# Xadow_Serial.net
KiCad netlist of a schematic drawn in EAGLE
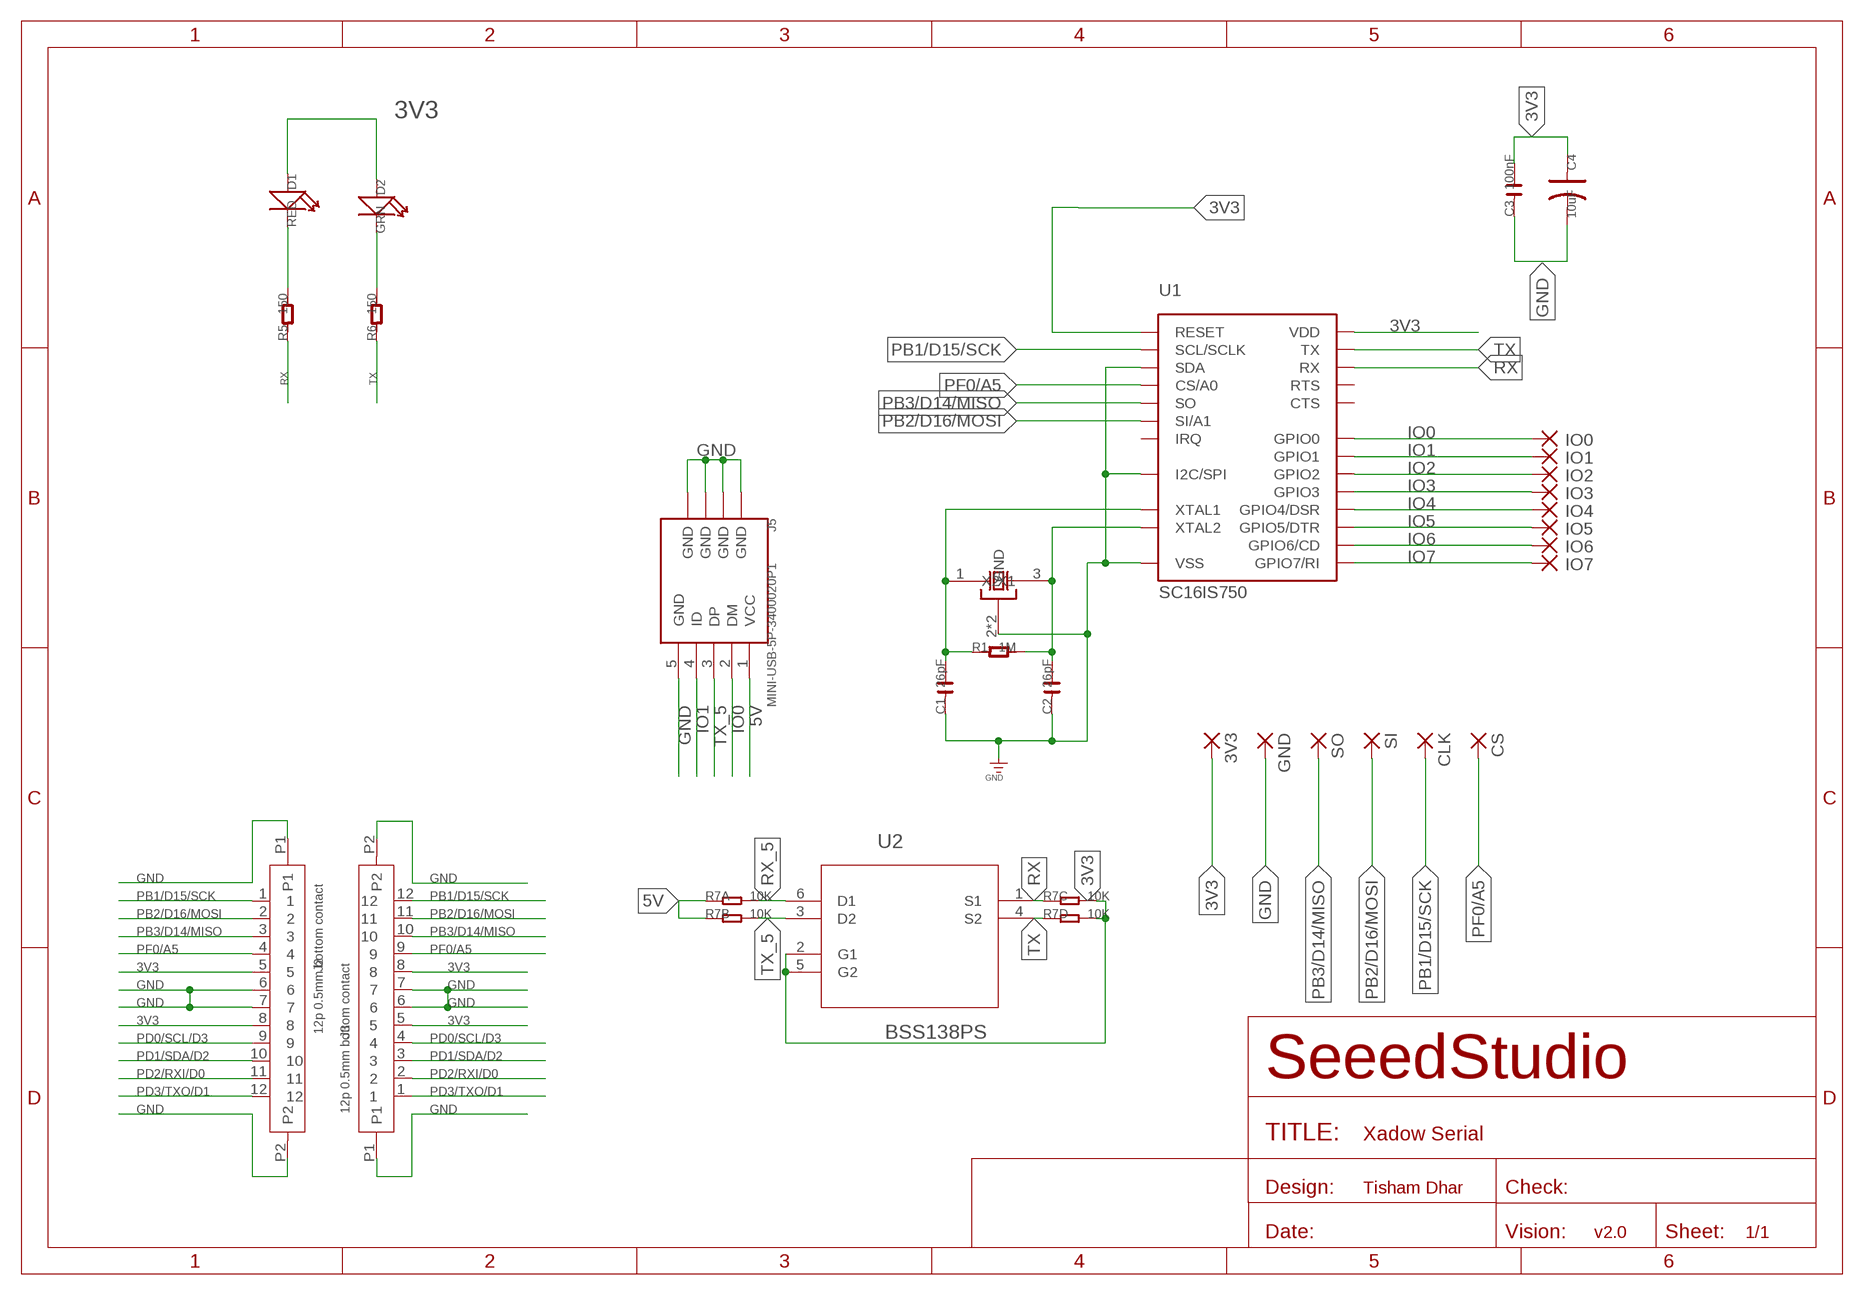
[diagram p0: schematic, sheet 1]

(export (version "E")
  (design (tool "Eeschema 10.0.6"))
  (components
    (comp (ref "3V3")
      (value "WIREPADSMD1,27-254")
      (footprint "eagle-import:SMD1,27-2,54")
      (libsource (lib "eagle-import") (part "WIREPADSMD1,27-254"))
    )
    (comp (ref "C1")
      (value "26pF")
      (footprint "eagle-import:C0603")
      (libsource (lib "eagle-import") (part "C-0603"))
    )
    (comp (ref "C2")
      (value "26pF")
      (footprint "eagle-import:C0603")
      (libsource (lib "eagle-import") (part "C-0603"))
    )
    (comp (ref "C3")
      (value "100nF")
      (footprint "eagle-import:C0603")
      (libsource (lib "eagle-import") (part "C-0603"))
    )
    (comp (ref "C4")
      (value "10uF")
      (footprint "eagle-import:AVX-A")
      (libsource (lib "eagle-import") (part "C-POLAR-A"))
    )
    (comp (ref "CLK")
      (value "WIREPADSMD1,27-254")
      (footprint "eagle-import:SMD1,27-2,54")
      (libsource (lib "eagle-import") (part "WIREPADSMD1,27-254"))
    )
    (comp (ref "CS")
      (value "WIREPADSMD1,27-254")
      (footprint "eagle-import:SMD1,27-2,54")
      (libsource (lib "eagle-import") (part "WIREPADSMD1,27-254"))
    )
    (comp (ref "D1")
      (value "RED")
      (footprint "eagle-import:LED0603")
      (libsource (lib "eagle-import") (part "LED"))
    )
    (comp (ref "D2")
      (value "GRN")
      (footprint "eagle-import:LED0603")
      (libsource (lib "eagle-import") (part "LED"))
    )
    (comp (ref "GND")
      (value "WIREPADSMD1,27-254")
      (footprint "eagle-import:SMD1,27-2,54")
      (libsource (lib "eagle-import") (part "WIREPADSMD1,27-254"))
    )
    (comp (ref "IO0")
      (value "WIREPADSMD1,27-254")
      (footprint "eagle-import:SMD1,27-2,54")
      (libsource (lib "eagle-import") (part "WIREPADSMD1,27-254"))
    )
    (comp (ref "IO1")
      (value "WIREPADSMD1,27-254")
      (footprint "eagle-import:SMD1,27-2,54")
      (libsource (lib "eagle-import") (part "WIREPADSMD1,27-254"))
    )
    (comp (ref "IO2")
      (value "WIREPADSMD1,27-254")
      (footprint "eagle-import:SMD1,27-2,54")
      (libsource (lib "eagle-import") (part "WIREPADSMD1,27-254"))
    )
    (comp (ref "IO3")
      (value "WIREPADSMD1,27-254")
      (footprint "eagle-import:SMD1,27-2,54")
      (libsource (lib "eagle-import") (part "WIREPADSMD1,27-254"))
    )
    (comp (ref "IO4")
      (value "WIREPADSMD1,27-254")
      (footprint "eagle-import:SMD1,27-2,54")
      (libsource (lib "eagle-import") (part "WIREPADSMD1,27-254"))
    )
    (comp (ref "IO5")
      (value "WIREPADSMD1,27-254")
      (footprint "eagle-import:SMD1,27-2,54")
      (libsource (lib "eagle-import") (part "WIREPADSMD1,27-254"))
    )
    (comp (ref "IO6")
      (value "WIREPADSMD1,27-254")
      (footprint "eagle-import:SMD1,27-2,54")
      (libsource (lib "eagle-import") (part "WIREPADSMD1,27-254"))
    )
    (comp (ref "IO7")
      (value "WIREPADSMD1,27-254")
      (footprint "eagle-import:SMD1,27-2,54")
      (libsource (lib "eagle-import") (part "WIREPADSMD1,27-254"))
    )
    (comp (ref "J2")
      (value "12p 0.5mm bottom contact")
      (footprint "eagle-import:12P-0.5")
      (libsource (lib "eagle-import") (part "FPC052002-12LT"))
    )
    (comp (ref "J3")
      (value "12p 0.5mm bottom contact")
      (footprint "eagle-import:12P-0.5")
      (libsource (lib "eagle-import") (part "FPC052002-12LT"))
    )
    (comp (ref "J5")
      (value "MINI-USB-5P-3400020P1")
      (footprint "eagle-import:MINI-B-SMD")
      (libsource (lib "eagle-import") (part "MINI-USB-5P-3400020P1"))
    )
    (comp (ref "R1")
      (value "1M")
      (footprint "eagle-import:R0603")
      (libsource (lib "eagle-import") (part "R-0603"))
    )
    (comp (ref "R5")
      (value "150")
      (footprint "eagle-import:R0603")
      (libsource (lib "eagle-import") (part "R-0603"))
    )
    (comp (ref "R6")
      (value "150")
      (footprint "eagle-import:R0603")
      (libsource (lib "eagle-import") (part "R-0603"))
    )
    (comp (ref "R7")
      (value "10K")
      (footprint "eagle-import:1206-8-3.3X2.4")
      (libsource (lib "eagle-import") (part "R-4R-1206"))
    )
    (comp (ref "SI")
      (value "WIREPADSMD1,27-254")
      (footprint "eagle-import:SMD1,27-2,54")
      (libsource (lib "eagle-import") (part "WIREPADSMD1,27-254"))
    )
    (comp (ref "SO")
      (value "WIREPADSMD1,27-254")
      (footprint "eagle-import:SMD1,27-2,54")
      (libsource (lib "eagle-import") (part "WIREPADSMD1,27-254"))
    )
    (comp (ref "U1")
      (value "SC16IS750")
      (footprint "eagle-import:TSSOP_24")
      (libsource (lib "eagle-import") (part "SC16IS750"))
    )
    (comp (ref "U2")
      (value "BSS138PS")
      (footprint "eagle-import:SOT65P210X110-6N")
      (libsource (lib "eagle-import") (part "BSS138PS"))
    )
    (comp (ref "X1")
      (value "CTS_32X25_SMD")
      (footprint "eagle-import:CTS_32X25")
      (libsource (lib "eagle-import") (part "CTS_32X25_SMD"))
    )
  )
  (nets
    (net (code "1") (name "/IO0") (class "Default")
      (node (ref "IO0") (pin "1") (pinfunction "P_1") (pintype "passive"))
      (node (ref "J5") (pin "2") (pinfunction "DM_2") (pintype "bidirectional"))
      (node (ref "U1") (pin "P$15") (pinfunction "GPIO0_P$15") (pintype "bidirectional"))
    )
    (net (code "2") (name "/IO1") (class "Default")
      (node (ref "IO1") (pin "1") (pinfunction "P_1") (pintype "passive"))
      (node (ref "J5") (pin "4") (pinfunction "ID_4") (pintype "bidirectional"))
      (node (ref "U1") (pin "P$16") (pinfunction "GPIO1_P$16") (pintype "bidirectional"))
    )
    (net (code "3") (name "/IO2") (class "Default")
      (node (ref "IO2") (pin "1") (pinfunction "P_1") (pintype "passive"))
      (node (ref "U1") (pin "P$17") (pinfunction "GPIO2_P$17") (pintype "bidirectional"))
    )
    (net (code "4") (name "/IO3") (class "Default")
      (node (ref "IO3") (pin "1") (pinfunction "P_1") (pintype "passive"))
      (node (ref "U1") (pin "P$18") (pinfunction "GPIO3_P$18") (pintype "bidirectional"))
    )
    (net (code "5") (name "/IO4") (class "Default")
      (node (ref "IO4") (pin "1") (pinfunction "P_1") (pintype "passive"))
      (node (ref "U1") (pin "P$20") (pinfunction "GPIO4/DSR_P$20") (pintype "bidirectional"))
    )
    (net (code "6") (name "/IO5") (class "Default")
      (node (ref "IO5") (pin "1") (pinfunction "P_1") (pintype "passive"))
      (node (ref "U1") (pin "P$21") (pinfunction "GPIO5/DTR_P$21") (pintype "bidirectional"))
    )
    (net (code "7") (name "/IO6") (class "Default")
      (node (ref "IO6") (pin "1") (pinfunction "P_1") (pintype "passive"))
      (node (ref "U1") (pin "P$22") (pinfunction "GPIO6/CD_P$22") (pintype "bidirectional"))
    )
    (net (code "8") (name "/IO7") (class "Default")
      (node (ref "IO7") (pin "1") (pinfunction "P_1") (pintype "passive"))
      (node (ref "U1") (pin "P$23") (pinfunction "GPIO7/RI_P$23") (pintype "bidirectional"))
    )
    (net (code "9") (name "/PD0{slash}SCL{slash}D3") (class "Default")
      (node (ref "J2") (pin "9") (pinfunction "9_9") (pintype "bidirectional"))
      (node (ref "J3") (pin "4") (pinfunction "4_4") (pintype "bidirectional"))
    )
    (net (code "10") (name "/PD1{slash}SDA{slash}D2") (class "Default")
      (node (ref "J2") (pin "10") (pinfunction "10_10") (pintype "bidirectional"))
      (node (ref "J3") (pin "3") (pinfunction "3_3") (pintype "bidirectional"))
    )
    (net (code "11") (name "/PD2{slash}RXI{slash}D0") (class "Default")
      (node (ref "J2") (pin "11") (pinfunction "11_11") (pintype "bidirectional"))
      (node (ref "J3") (pin "2") (pinfunction "2_2") (pintype "bidirectional"))
    )
    (net (code "12") (name "/PD3{slash}TXO{slash}D1") (class "Default")
      (node (ref "J2") (pin "12") (pinfunction "12_12") (pintype "bidirectional"))
      (node (ref "J3") (pin "1") (pinfunction "1_1") (pintype "bidirectional"))
    )
    (net (code "13") (name "3V3") (class "Default")
      (node (ref "3V3") (pin "1") (pinfunction "P_1") (pintype "passive"))
      (node (ref "C3") (pin "2") (pinfunction "2_2") (pintype "bidirectional"))
      (node (ref "C4") (pin "+") (pinfunction "1_+") (pintype "bidirectional"))
      (node (ref "D1") (pin "+") (pinfunction "+_+") (pintype "passive"))
      (node (ref "D2") (pin "+") (pinfunction "+_+") (pintype "passive"))
      (node (ref "J2") (pin "5") (pinfunction "5_5") (pintype "bidirectional"))
      (node (ref "J2") (pin "8") (pinfunction "8_8") (pintype "bidirectional"))
      (node (ref "J3") (pin "5") (pinfunction "5_5") (pintype "bidirectional"))
      (node (ref "J3") (pin "8") (pinfunction "8_8") (pintype "bidirectional"))
      (node (ref "R7") (pin "5") (pinfunction "2_5") (pintype "passive"))
      (node (ref "R7") (pin "6") (pinfunction "2_6") (pintype "passive"))
      (node (ref "U1") (pin "P$4") (pinfunction "RESET_P$4") (pintype "input"))
      (node (ref "U1") (pin "P$7") (pinfunction "VDD_P$7") (pintype "power_in"))
      (node (ref "U2") (pin "2") (pinfunction "G1_2") (pintype "input"))
      (node (ref "U2") (pin "5") (pinfunction "G2_5") (pintype "input"))
    )
    (net (code "14") (name "5V") (class "Default")
      (node (ref "J5") (pin "1") (pinfunction "VCC_1") (pintype "bidirectional"))
      (node (ref "R7") (pin "1") (pinfunction "1_1") (pintype "passive"))
      (node (ref "R7") (pin "2") (pinfunction "1_2") (pintype "passive"))
    )
    (net (code "15") (name "GND") (class "Default")
      (node (ref "C1") (pin "1") (pinfunction "1_1") (pintype "bidirectional"))
      (node (ref "C2") (pin "1") (pinfunction "1_1") (pintype "bidirectional"))
      (node (ref "C3") (pin "1") (pinfunction "1_1") (pintype "bidirectional"))
      (node (ref "C4") (pin "-") (pinfunction "2_-") (pintype "bidirectional"))
      (node (ref "GND") (pin "1") (pinfunction "P_1") (pintype "passive"))
      (node (ref "J2") (pin "6") (pinfunction "6_6") (pintype "bidirectional"))
      (node (ref "J2") (pin "7") (pinfunction "7_7") (pintype "bidirectional"))
      (node (ref "J2") (pin "P1") (pinfunction "P1_P1") (pintype "bidirectional"))
      (node (ref "J2") (pin "P2") (pinfunction "P2_P2") (pintype "bidirectional"))
      (node (ref "J3") (pin "6") (pinfunction "6_6") (pintype "bidirectional"))
      (node (ref "J3") (pin "7") (pinfunction "7_7") (pintype "bidirectional"))
      (node (ref "J3") (pin "P1") (pinfunction "P1_P1") (pintype "bidirectional"))
      (node (ref "J3") (pin "P2") (pinfunction "P2_P2") (pintype "bidirectional"))
      (node (ref "J5") (pin "5") (pinfunction "GND_5") (pintype "bidirectional"))
      (node (ref "J5") (pin "P$1") (pinfunction "GND_P$1") (pintype "bidirectional"))
      (node (ref "J5") (pin "P$2") (pinfunction "GND_P$2") (pintype "bidirectional"))
      (node (ref "J5") (pin "P$3") (pinfunction "GND_P$3") (pintype "bidirectional"))
      (node (ref "J5") (pin "P$4") (pinfunction "GND_P$4") (pintype "bidirectional"))
      (node (ref "U1") (pin "P$13") (pinfunction "SDA_P$13") (pintype "bidirectional"))
      (node (ref "U1") (pin "P$19") (pinfunction "VSS_P$19") (pintype "power_in"))
      (node (ref "U1") (pin "P$8") (pinfunction "I2C/SPI_P$8") (pintype "bidirectional"))
      (node (ref "X1") (pin "2") (pinfunction "GND_2") (pintype "power_in"))
      (node (ref "X1") (pin "4") (pinfunction "GND_4") (pintype "power_in"))
    )
    (net (code "16") (name "Net-(D1-Pad-)") (class "Default")
      (node (ref "D1") (pin "-") (pinfunction "-_-") (pintype "passive"))
      (node (ref "R5") (pin "2") (pinfunction "2_2") (pintype "bidirectional"))
    )
    (net (code "17") (name "Net-(D2-Pad-)") (class "Default")
      (node (ref "D2") (pin "-") (pinfunction "-_-") (pintype "passive"))
      (node (ref "R6") (pin "2") (pinfunction "2_2") (pintype "bidirectional"))
    )
    (net (code "18") (name "Net-(U1-XTAL1)") (class "Default")
      (node (ref "C1") (pin "2") (pinfunction "2_2") (pintype "bidirectional"))
      (node (ref "R1") (pin "1") (pinfunction "1_1") (pintype "bidirectional"))
      (node (ref "U1") (pin "P$5") (pinfunction "XTAL1_P$5") (pintype "input"))
      (node (ref "X1") (pin "1") (pinfunction "X1_1") (pintype "bidirectional"))
    )
    (net (code "19") (name "Net-(U1-XTAL2)") (class "Default")
      (node (ref "C2") (pin "2") (pinfunction "2_2") (pintype "bidirectional"))
      (node (ref "R1") (pin "2") (pinfunction "2_2") (pintype "bidirectional"))
      (node (ref "U1") (pin "P$6") (pinfunction "XTAL2_P$6") (pintype "output"))
      (node (ref "X1") (pin "3") (pinfunction "X2_3") (pintype "bidirectional"))
    )
    (net (code "20") (name "PB1{slash}D15{slash}SCK") (class "Default")
      (node (ref "CLK") (pin "1") (pinfunction "P_1") (pintype "passive"))
      (node (ref "J2") (pin "1") (pinfunction "1_1") (pintype "bidirectional"))
      (node (ref "J3") (pin "12") (pinfunction "12_12") (pintype "bidirectional"))
      (node (ref "U1") (pin "P$12") (pinfunction "SCL/SCLK_P$12") (pintype "input"))
    )
    (net (code "21") (name "PB2{slash}D16{slash}MOSI") (class "Default")
      (node (ref "J2") (pin "2") (pinfunction "2_2") (pintype "bidirectional"))
      (node (ref "J3") (pin "11") (pinfunction "11_11") (pintype "bidirectional"))
      (node (ref "SI") (pin "1") (pinfunction "P_1") (pintype "passive"))
      (node (ref "U1") (pin "P$10") (pinfunction "SI/A1_P$10") (pintype "input"))
    )
    (net (code "22") (name "PB3{slash}D14{slash}MISO") (class "Default")
      (node (ref "J2") (pin "3") (pinfunction "3_3") (pintype "bidirectional"))
      (node (ref "J3") (pin "10") (pinfunction "10_10") (pintype "bidirectional"))
      (node (ref "SO") (pin "1") (pinfunction "P_1") (pintype "passive"))
      (node (ref "U1") (pin "P$11") (pinfunction "SO_P$11") (pintype "output"))
    )
    (net (code "23") (name "PF0{slash}A5") (class "Default")
      (node (ref "CS") (pin "1") (pinfunction "P_1") (pintype "passive"))
      (node (ref "J2") (pin "4") (pinfunction "4_4") (pintype "bidirectional"))
      (node (ref "J3") (pin "9") (pinfunction "9_9") (pintype "bidirectional"))
      (node (ref "U1") (pin "P$9") (pinfunction "CS/A0_P$9") (pintype "input"))
    )
    (net (code "24") (name "RX") (class "Default")
      (node (ref "R5") (pin "1") (pinfunction "1_1") (pintype "bidirectional"))
      (node (ref "R7") (pin "3") (pinfunction "1_3") (pintype "passive"))
      (node (ref "U1") (pin "P$3") (pinfunction "RX_P$3") (pintype "input"))
      (node (ref "U2") (pin "1") (pinfunction "S1_1") (pintype "output"))
    )
    (net (code "25") (name "RX_5") (class "Default")
      (node (ref "R7") (pin "8") (pinfunction "2_8") (pintype "passive"))
      (node (ref "U2") (pin "6") (pinfunction "D1_6") (pintype "input"))
    )
    (net (code "26") (name "TX") (class "Default")
      (node (ref "R6") (pin "1") (pinfunction "1_1") (pintype "bidirectional"))
      (node (ref "R7") (pin "4") (pinfunction "1_4") (pintype "passive"))
      (node (ref "U1") (pin "P$2") (pinfunction "TX_P$2") (pintype "output"))
      (node (ref "U2") (pin "4") (pinfunction "S2_4") (pintype "output"))
    )
    (net (code "27") (name "TX_5") (class "Default")
      (node (ref "J5") (pin "3") (pinfunction "DP_3") (pintype "bidirectional"))
      (node (ref "R7") (pin "7") (pinfunction "2_7") (pintype "passive"))
      (node (ref "U2") (pin "3") (pinfunction "D2_3") (pintype "input"))
    )
    (net (code "28") (name "unconnected-(U1-CTS-PadP$1)") (class "Default")
      (node (ref "U1") (pin "P$1") (pinfunction "CTS_P$1") (pintype "input"))
    )
    (net (code "29") (name "unconnected-(U1-IRQ-PadP$14)") (class "Default")
      (node (ref "U1") (pin "P$14") (pinfunction "IRQ_P$14") (pintype "output"))
    )
    (net (code "30") (name "unconnected-(U1-RTS-PadP$24)") (class "Default")
      (node (ref "U1") (pin "P$24") (pinfunction "RTS_P$24") (pintype "output"))
    )
  )
)
